# AirOwlPCBV7final.net
KiCad netlist of a schematic drawn in EAGLE
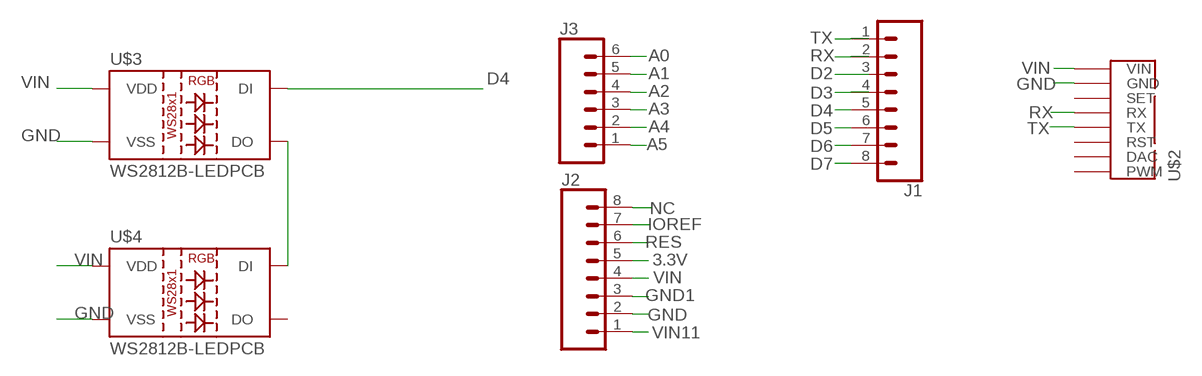
[diagram p0: schematic, sheet 1]

(export (version "E")
  (design (tool "Eeschema 10.0.6"))
  (components
    (comp (ref "J1")
      (value "CONN_08\"")
      (footprint "eagle-import:1X08")
      (libsource (lib "eagle-import") (part "CONN_08{dblquote}"))
    )
    (comp (ref "J2")
      (value "CONN_08\"")
      (footprint "eagle-import:1X08")
      (libsource (lib "eagle-import") (part "CONN_08{dblquote}"))
    )
    (comp (ref "J3")
      (value "CONN_06SILK_FEMALE_PTH")
      (footprint "eagle-import:1X06")
      (libsource (lib "eagle-import") (part "CONN_06SILK_FEMALE_PTH"))
    )
    (comp (ref "U$2")
      (value "WINSEN_CONNECTOR")
      (footprint "eagle-import:WINSEN_CONNECTOR")
      (libsource (lib "eagle-import") (part "WINSEN_CONNECTOR"))
    )
    (comp (ref "U$3")
      (value "WS2812B-LEDPCB")
      (footprint "eagle-import:WS2812B-LEDPCB")
      (libsource (lib "eagle-import") (part "WS2812B-LEDPCB"))
    )
    (comp (ref "U$4")
      (value "WS2812B-LEDPCB")
      (footprint "eagle-import:WS2812B-LEDPCB")
      (libsource (lib "eagle-import") (part "WS2812B-LEDPCB"))
    )
  )
  (nets
    (net (code "1") (name "/3.3V") (class "Default")
      (node (ref "J2") (pin "5") (pinfunction "5_5") (pintype "passive"))
    )
    (net (code "2") (name "/A0") (class "Default")
      (node (ref "J3") (pin "6") (pinfunction "6_6") (pintype "passive"))
    )
    (net (code "3") (name "/A1") (class "Default")
      (node (ref "J3") (pin "5") (pinfunction "5_5") (pintype "passive"))
    )
    (net (code "4") (name "/A2") (class "Default")
      (node (ref "J3") (pin "4") (pinfunction "4_4") (pintype "passive"))
    )
    (net (code "5") (name "/A3") (class "Default")
      (node (ref "J3") (pin "3") (pinfunction "3_3") (pintype "passive"))
    )
    (net (code "6") (name "/A4") (class "Default")
      (node (ref "J3") (pin "2") (pinfunction "2_2") (pintype "passive"))
    )
    (net (code "7") (name "/A5") (class "Default")
      (node (ref "J3") (pin "1") (pinfunction "1_1") (pintype "passive"))
    )
    (net (code "8") (name "/D2") (class "Default")
      (node (ref "J1") (pin "3") (pinfunction "3_3") (pintype "passive"))
    )
    (net (code "9") (name "/D3") (class "Default")
      (node (ref "J1") (pin "4") (pinfunction "4_4") (pintype "passive"))
    )
    (net (code "10") (name "/D4") (class "Default")
      (node (ref "J1") (pin "5") (pinfunction "5_5") (pintype "passive"))
      (node (ref "U$3") (pin "4") (pinfunction "DI_4") (pintype "bidirectional"))
    )
    (net (code "11") (name "/D5") (class "Default")
      (node (ref "J1") (pin "6") (pinfunction "6_6") (pintype "passive"))
    )
    (net (code "12") (name "/D6") (class "Default")
      (node (ref "J1") (pin "7") (pinfunction "7_7") (pintype "passive"))
    )
    (net (code "13") (name "/D7") (class "Default")
      (node (ref "J1") (pin "8") (pinfunction "8_8") (pintype "passive"))
    )
    (net (code "14") (name "/GND") (class "Default")
      (node (ref "J2") (pin "2") (pinfunction "2_2") (pintype "passive"))
      (node (ref "U$2") (pin "P$8") (pinfunction "GND_P$8") (pintype "bidirectional"))
      (node (ref "U$3") (pin "3") (pinfunction "VSS_3") (pintype "bidirectional"))
      (node (ref "U$4") (pin "3") (pinfunction "VSS_3") (pintype "bidirectional"))
    )
    (net (code "15") (name "/GND1") (class "Default")
      (node (ref "J2") (pin "3") (pinfunction "3_3") (pintype "passive"))
    )
    (net (code "16") (name "/IOREF") (class "Default")
      (node (ref "J2") (pin "7") (pinfunction "7_7") (pintype "passive"))
    )
    (net (code "17") (name "/NC") (class "Default")
      (node (ref "J2") (pin "8") (pinfunction "8_8") (pintype "passive"))
    )
    (net (code "18") (name "/RES") (class "Default")
      (node (ref "J2") (pin "6") (pinfunction "6_6") (pintype "passive"))
    )
    (net (code "19") (name "/RX") (class "Default")
      (node (ref "J1") (pin "2") (pinfunction "2_2") (pintype "passive"))
      (node (ref "U$2") (pin "P$6") (pinfunction "RX_P$6") (pintype "bidirectional"))
    )
    (net (code "20") (name "/TX") (class "Default")
      (node (ref "J1") (pin "1") (pinfunction "1_1") (pintype "passive"))
      (node (ref "U$2") (pin "P$5") (pinfunction "TX_P$5") (pintype "bidirectional"))
    )
    (net (code "21") (name "/VIN") (class "Default")
      (node (ref "J2") (pin "4") (pinfunction "4_4") (pintype "passive"))
      (node (ref "U$2") (pin "P$9") (pinfunction "VIN_P$9") (pintype "bidirectional"))
      (node (ref "U$3") (pin "1") (pinfunction "VDD_1") (pintype "bidirectional"))
      (node (ref "U$4") (pin "1") (pinfunction "VDD_1") (pintype "bidirectional"))
    )
    (net (code "22") (name "/VIN11") (class "Default")
      (node (ref "J2") (pin "1") (pinfunction "1_1") (pintype "passive"))
    )
    (net (code "23") (name "Net-(U$3-DO)") (class "Default")
      (node (ref "U$3") (pin "2") (pinfunction "DO_2") (pintype "bidirectional"))
      (node (ref "U$4") (pin "4") (pinfunction "DI_4") (pintype "bidirectional"))
    )
    (net (code "24") (name "unconnected-(U$2-DAC-PadP$3)") (class "Default")
      (node (ref "U$2") (pin "P$3") (pinfunction "DAC_P$3") (pintype "bidirectional"))
    )
    (net (code "25") (name "unconnected-(U$2-PWM-PadP$2)") (class "Default")
      (node (ref "U$2") (pin "P$2") (pinfunction "PWM_P$2") (pintype "bidirectional"))
    )
    (net (code "26") (name "unconnected-(U$2-RST-PadP$4)") (class "Default")
      (node (ref "U$2") (pin "P$4") (pinfunction "RST_P$4") (pintype "bidirectional"))
    )
    (net (code "27") (name "unconnected-(U$2-SET-PadP$7)") (class "Default")
      (node (ref "U$2") (pin "P$7") (pinfunction "SET_P$7") (pintype "bidirectional"))
    )
    (net (code "28") (name "unconnected-(U$4-DO-Pad2)") (class "Default")
      (node (ref "U$4") (pin "2") (pinfunction "DO_2") (pintype "bidirectional"))
    )
  )
)
